# AVkings_mazesolvver-mz1__Sheet_1_2025-12.net
KiCad netlist of a schematic drawn in Altium Designer
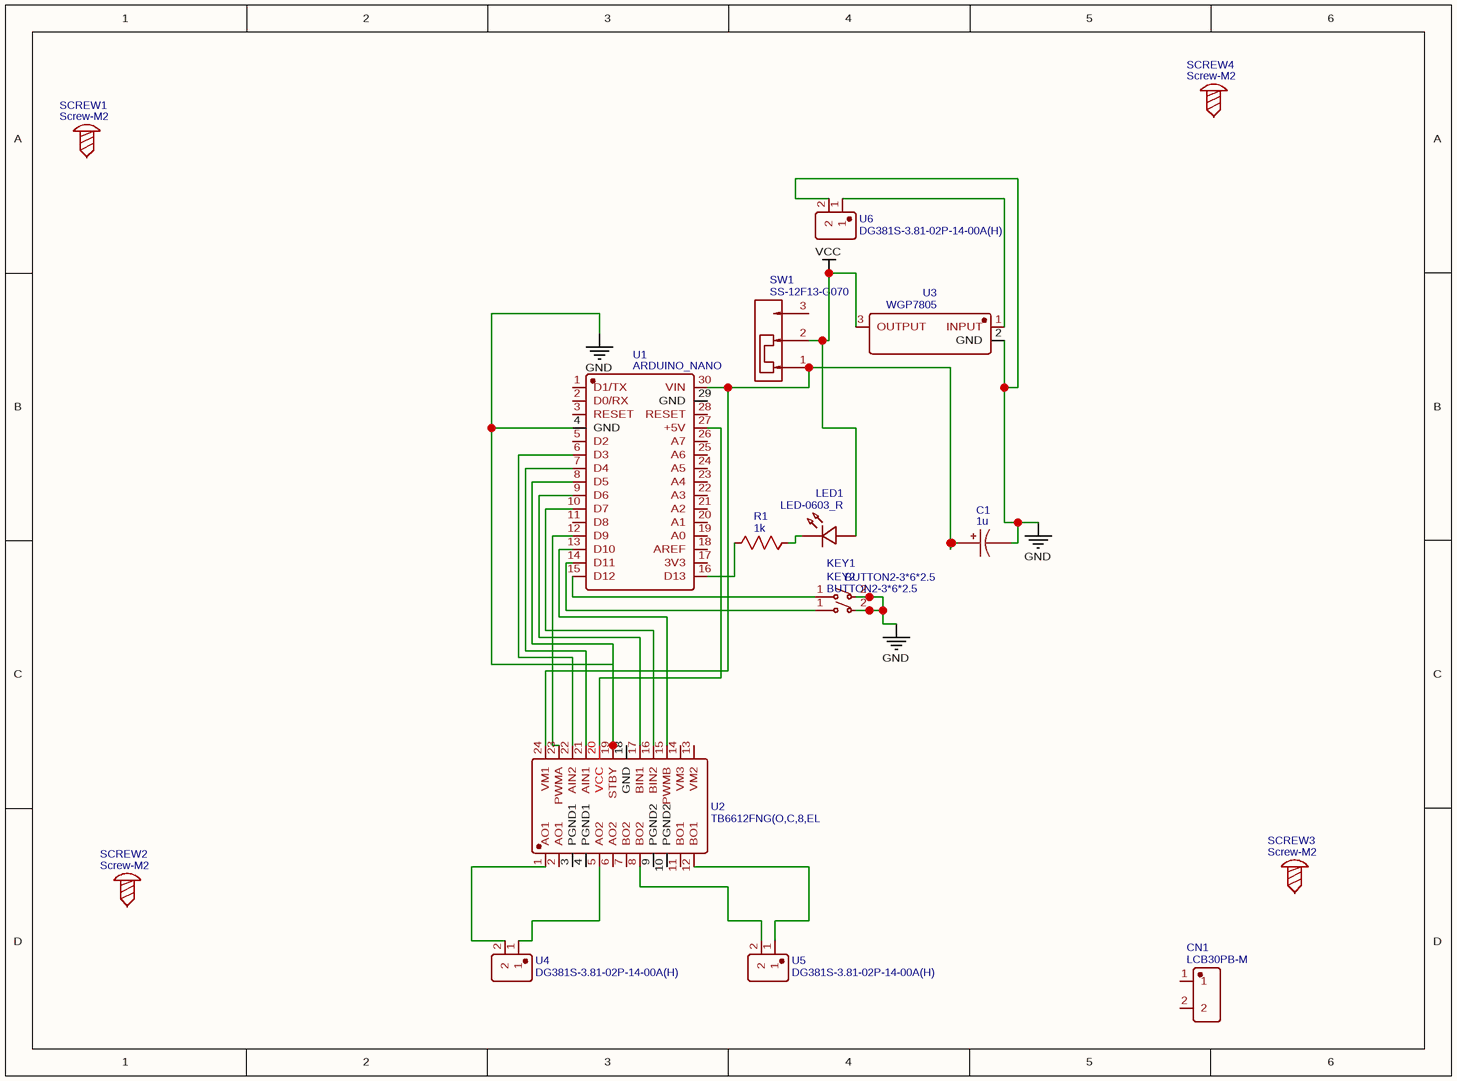
[diagram p0: AVkings_mazesolvver-mz1__Sheet_1_2025-12-17.schdoc]

(export (version "E")
  (design (tool "Eeschema 10.0.6"))
  (components
    (comp (ref "C1")
      (value "1u")
      (fields (field (name "CONTRIBUTOR") "LCEDA_Lib"))
      (libsource (lib "altium-import") (part "root_0_1u_"))
    )
    (comp (ref "CN1")
      (value "LCB30PB-M")
      (fields (field (name "MANUFACTURER") "AMASS(艾迈斯)") (field (name "CONTRIBUTOR") "lcsc"))
      (libsource (lib "altium-import") (part "root_0_LCB30PB-M_"))
    )
    (comp (ref "KEY1")
      (value "BUTTON2-3*6*2.5")
      (fields (field (name "CONTRIBUTOR") "LCSC"))
      (libsource (lib "altium-import") (part "root_0_BUTTON2-3*6*2.5_"))
    )
    (comp (ref "KEY2")
      (value "BUTTON2-3*6*2.5")
      (fields (field (name "CONTRIBUTOR") "LCSC"))
      (libsource (lib "altium-import") (part "root_0_BUTTON2-3*6*2.5_"))
    )
    (comp (ref "LED1")
      (value "LED-0603_R")
      (fields
        (field (name "MANUFACTURER") "EVERLIGHT(台湾亿光)")
        (field (name "MANUFACTURER PART") "19-217/R6C-AL1M2VY/3T")
        (field (name "CONTRIBUTOR") "LCEDA_01")
      )
      (libsource (lib "altium-import") (part "root_0_LED-0603_R_"))
    )
    (comp (ref "R1")
      (value "1k")
      (fields (field (name "CONTRIBUTOR") "LCEDA_Lib"))
      (libsource (lib "altium-import") (part "root_0_1k_"))
    )
    (comp (ref "SCREW1")
      (value "Screw-M2")
      (fields (field (name "CONTRIBUTOR") "EasyEDA"))
      (libsource (lib "altium-import") (part "root_0_Screw-M2_"))
    )
    (comp (ref "SCREW2")
      (value "Screw-M2")
      (fields (field (name "CONTRIBUTOR") "EasyEDA"))
      (libsource (lib "altium-import") (part "root_0_Screw-M2_"))
    )
    (comp (ref "SCREW3")
      (value "Screw-M2")
      (fields (field (name "CONTRIBUTOR") "EasyEDA"))
      (libsource (lib "altium-import") (part "root_0_Screw-M2_"))
    )
    (comp (ref "SCREW4")
      (value "Screw-M2")
      (fields (field (name "CONTRIBUTOR") "EasyEDA"))
      (libsource (lib "altium-import") (part "root_0_Screw-M2_"))
    )
    (comp (ref "SW1")
      (value "SS-12F13-G070")
      (fields (field (name "MANUFACTURER") "G-Switch(品赞)") (field (name "CONTRIBUTOR") "LCSC"))
      (libsource (lib "altium-import") (part "root_1_SS-12F13-G070_"))
    )
    (comp (ref "U1")
      (value "ARDUINO_NANO")
      (fields (field (name "CONTRIBUTOR") "lcsc"))
      (libsource (lib "altium-import") (part "root_0_ARDUINO_NANO_"))
    )
    (comp (ref "U2")
      (value "TB6612FNG(O,C,8,EL")
      (fields (field (name "MANUFACTURER") "TOSHIBA(东芝)"))
      (libsource (lib "altium-import") (part "root_1_TB6612FNG(O,C,8,EL_"))
    )
    (comp (ref "U3")
      (value "WGP7805")
      (fields (field (name "MANUFACTURER") "Wild Goose(威谷)") (field (name "CONTRIBUTOR") "lcsc"))
      (libsource (lib "altium-import") (part "root_0_WGP7805_"))
    )
    (comp (ref "U4")
      (value "DG381S-3.81-02P-14-00A(H)")
      (fields (field (name "MANUFACTURER") "DEGSON(高正/高松)") (field (name "CONTRIBUTOR") "LCSC"))
      (libsource (lib "altium-import") (part "root_3_DG381S-3.81-02P-14-00A(H)_"))
    )
    (comp (ref "U5")
      (value "DG381S-3.81-02P-14-00A(H)")
      (fields (field (name "MANUFACTURER") "DEGSON(高正/高松)") (field (name "CONTRIBUTOR") "LCSC"))
      (libsource (lib "altium-import") (part "root_3_DG381S-3.81-02P-14-00A(H)_"))
    )
    (comp (ref "U6")
      (value "DG381S-3.81-02P-14-00A(H)")
      (fields (field (name "MANUFACTURER") "DEGSON(高正/高松)") (field (name "CONTRIBUTOR") "LCSC"))
      (libsource (lib "altium-import") (part "root_3_DG381S-3.81-02P-14-00A(H)_"))
    )
  )
  (nets
    (net (code "1") (name "GND") (class "Default")
      (node (ref "C1") (pin "2") (pinfunction "2_2") (pintype "passive"))
      (node (ref "KEY1") (pin "2") (pinfunction "2_2") (pintype "passive"))
      (node (ref "KEY2") (pin "2") (pinfunction "2_2") (pintype "passive"))
      (node (ref "U1") (pin "4") (pinfunction "GND_4") (pintype "passive"))
      (node (ref "U1") (pin "8") (pinfunction "D5_8") (pintype "passive"))
      (node (ref "U2") (pin "19") (pinfunction "STBY_19") (pintype "passive"))
      (node (ref "U3") (pin "2") (pinfunction "GND_2") (pintype "passive"))
      (node (ref "U6") (pin "2") (pinfunction "2_2") (pintype "passive"))
    )
    (net (code "2") (name "Net-(LED1-Pad2)") (class "Default")
      (node (ref "LED1") (pin "2") (pinfunction "2_2") (pintype "passive"))
      (node (ref "R1") (pin "2") (pinfunction "2_2") (pintype "passive"))
    )
    (net (code "3") (name "Net-(U1-+5V)") (class "Default")
      (node (ref "U1") (pin "27") (pinfunction "+5V_27") (pintype "passive"))
      (node (ref "U2") (pin "20") (pinfunction "VCC_20") (pintype "passive"))
    )
    (net (code "4") (name "Net-(U1-D3)") (class "Default")
      (node (ref "U1") (pin "6") (pinfunction "D3_6") (pintype "passive"))
      (node (ref "U2") (pin "22") (pinfunction "AIN2_22") (pintype "passive"))
    )
    (net (code "5") (name "Net-(U1-D4)") (class "Default")
      (node (ref "U1") (pin "7") (pinfunction "D4_7") (pintype "passive"))
      (node (ref "U2") (pin "21") (pinfunction "AIN1_21") (pintype "passive"))
    )
    (net (code "6") (name "Net-(U1-D6)") (class "Default")
      (node (ref "U1") (pin "9") (pinfunction "D6_9") (pintype "passive"))
      (node (ref "U2") (pin "17") (pinfunction "BIN1_17") (pintype "passive"))
    )
    (net (code "7") (name "Net-(U1-D7)") (class "Default")
      (node (ref "U1") (pin "10") (pinfunction "D7_10") (pintype "passive"))
      (node (ref "U2") (pin "16") (pinfunction "BIN2_16") (pintype "passive"))
    )
    (net (code "8") (name "Net-(U1-D9)") (class "Default")
      (node (ref "U1") (pin "12") (pinfunction "D9_12") (pintype "passive"))
      (node (ref "U2") (pin "23") (pinfunction "PWMA_23") (pintype "passive"))
    )
    (net (code "9") (name "Net-(U1-D10)") (class "Default")
      (node (ref "U1") (pin "13") (pinfunction "D10_13") (pintype "passive"))
      (node (ref "U2") (pin "15") (pinfunction "PWMB_15") (pintype "passive"))
    )
    (net (code "10") (name "Net-(U1-D11)") (class "Default")
      (node (ref "KEY2") (pin "1") (pinfunction "1_1") (pintype "passive"))
      (node (ref "U1") (pin "14") (pinfunction "D11_14") (pintype "passive"))
    )
    (net (code "11") (name "Net-(U1-D12)") (class "Default")
      (node (ref "KEY1") (pin "1") (pinfunction "1_1") (pintype "passive"))
      (node (ref "U1") (pin "15") (pinfunction "D12_15") (pintype "passive"))
    )
    (net (code "12") (name "Net-(U1-D13)") (class "Default")
      (node (ref "R1") (pin "1") (pinfunction "1_1") (pintype "passive"))
      (node (ref "U1") (pin "16") (pinfunction "D13_16") (pintype "passive"))
    )
    (net (code "13") (name "Net-(U1-VIN)") (class "Default")
      (node (ref "C1") (pin "1") (pinfunction "1_1") (pintype "passive"))
      (node (ref "SW1") (pin "1") (pinfunction "1_1") (pintype "passive"))
      (node (ref "U1") (pin "30") (pinfunction "VIN_30") (pintype "passive"))
      (node (ref "U2") (pin "24") (pinfunction "VM1_24") (pintype "passive"))
    )
    (net (code "14") (name "Net-(U2-AO1-Pad1)") (class "Default")
      (node (ref "U2") (pin "1") (pinfunction "AO1_1") (pintype "passive"))
      (node (ref "U4") (pin "2") (pinfunction "2_2") (pintype "passive"))
    )
    (net (code "15") (name "Net-(U2-AO2-Pad5)") (class "Default")
      (node (ref "U2") (pin "5") (pinfunction "AO2_5") (pintype "passive"))
      (node (ref "U4") (pin "1") (pinfunction "1_1") (pintype "passive"))
    )
    (net (code "16") (name "Net-(U2-BO1-Pad12)") (class "Default")
      (node (ref "U2") (pin "12") (pinfunction "BO1_12") (pintype "passive"))
      (node (ref "U5") (pin "1") (pinfunction "1_1") (pintype "passive"))
    )
    (net (code "17") (name "Net-(U2-BO2-Pad8)") (class "Default")
      (node (ref "U2") (pin "8") (pinfunction "BO2_8") (pintype "passive"))
      (node (ref "U5") (pin "2") (pinfunction "2_2") (pintype "passive"))
    )
    (net (code "18") (name "Net-(U3-INPUT)") (class "Default")
      (node (ref "U3") (pin "1") (pinfunction "INPUT_1") (pintype "passive"))
      (node (ref "U6") (pin "1") (pinfunction "1_1") (pintype "passive"))
    )
    (net (code "19") (name "VCC") (class "Default")
      (node (ref "LED1") (pin "1") (pinfunction "1_1") (pintype "passive"))
      (node (ref "SW1") (pin "2") (pinfunction "2_2") (pintype "passive"))
      (node (ref "U3") (pin "3") (pinfunction "OUTPUT_3") (pintype "passive"))
    )
    (net (code "20") (name "unconnected-(CN1-Pad1)") (class "Default")
      (node (ref "CN1") (pin "1") (pinfunction "1_1") (pintype "passive"))
    )
    (net (code "21") (name "unconnected-(CN1-Pad2)") (class "Default")
      (node (ref "CN1") (pin "2") (pinfunction "2_2") (pintype "passive"))
    )
    (net (code "22") (name "unconnected-(SCREW1-Pad1)") (class "Default")
      (node (ref "SCREW1") (pin "1") (pinfunction "1_1") (pintype "passive"))
    )
    (net (code "23") (name "unconnected-(SCREW2-Pad1)") (class "Default")
      (node (ref "SCREW2") (pin "1") (pinfunction "1_1") (pintype "passive"))
    )
    (net (code "24") (name "unconnected-(SCREW3-Pad1)") (class "Default")
      (node (ref "SCREW3") (pin "1") (pinfunction "1_1") (pintype "passive"))
    )
    (net (code "25") (name "unconnected-(SCREW4-Pad1)") (class "Default")
      (node (ref "SCREW4") (pin "1") (pinfunction "1_1") (pintype "passive"))
    )
    (net (code "26") (name "unconnected-(SW1-Pad3)") (class "Default")
      (node (ref "SW1") (pin "3") (pinfunction "3_3") (pintype "passive"))
    )
    (net (code "27") (name "unconnected-(U1-3V3-Pad17)") (class "Default")
      (node (ref "U1") (pin "17") (pinfunction "3V3_17") (pintype "passive"))
    )
    (net (code "28") (name "unconnected-(U1-A0-Pad19)") (class "Default")
      (node (ref "U1") (pin "19") (pinfunction "A0_19") (pintype "passive"))
    )
    (net (code "29") (name "unconnected-(U1-A1-Pad20)") (class "Default")
      (node (ref "U1") (pin "20") (pinfunction "A1_20") (pintype "passive"))
    )
    (net (code "30") (name "unconnected-(U1-A2-Pad21)") (class "Default")
      (node (ref "U1") (pin "21") (pinfunction "A2_21") (pintype "passive"))
    )
    (net (code "31") (name "unconnected-(U1-A3-Pad22)") (class "Default")
      (node (ref "U1") (pin "22") (pinfunction "A3_22") (pintype "passive"))
    )
    (net (code "32") (name "unconnected-(U1-A4-Pad23)") (class "Default")
      (node (ref "U1") (pin "23") (pinfunction "A4_23") (pintype "passive"))
    )
    (net (code "33") (name "unconnected-(U1-A5-Pad24)") (class "Default")
      (node (ref "U1") (pin "24") (pinfunction "A5_24") (pintype "passive"))
    )
    (net (code "34") (name "unconnected-(U1-A6-Pad25)") (class "Default")
      (node (ref "U1") (pin "25") (pinfunction "A6_25") (pintype "passive"))
    )
    (net (code "35") (name "unconnected-(U1-A7-Pad26)") (class "Default")
      (node (ref "U1") (pin "26") (pinfunction "A7_26") (pintype "passive"))
    )
    (net (code "36") (name "unconnected-(U1-AREF-Pad18)") (class "Default")
      (node (ref "U1") (pin "18") (pinfunction "AREF_18") (pintype "passive"))
    )
    (net (code "37") (name "unconnected-(U1-D0{slash}RX-Pad2)") (class "Default")
      (node (ref "U1") (pin "2") (pinfunction "D0/RX_2") (pintype "passive"))
    )
    (net (code "38") (name "unconnected-(U1-D1{slash}TX-Pad1)") (class "Default")
      (node (ref "U1") (pin "1") (pinfunction "D1/TX_1") (pintype "passive"))
    )
    (net (code "39") (name "unconnected-(U1-D2-Pad5)") (class "Default")
      (node (ref "U1") (pin "5") (pinfunction "D2_5") (pintype "passive"))
    )
    (net (code "40") (name "unconnected-(U1-D8-Pad11)") (class "Default")
      (node (ref "U1") (pin "11") (pinfunction "D8_11") (pintype "passive"))
    )
    (net (code "41") (name "unconnected-(U1-GND-Pad29)") (class "Default")
      (node (ref "U1") (pin "29") (pinfunction "GND_29") (pintype "passive"))
    )
    (net (code "42") (name "unconnected-(U1-RESET-Pad3)") (class "Default")
      (node (ref "U1") (pin "3") (pinfunction "RESET_3") (pintype "passive"))
    )
    (net (code "43") (name "unconnected-(U1-RESET-Pad28)") (class "Default")
      (node (ref "U1") (pin "28") (pinfunction "RESET_28") (pintype "passive"))
    )
    (net (code "44") (name "unconnected-(U2-AO1-Pad2)") (class "Default")
      (node (ref "U2") (pin "2") (pinfunction "AO1_2") (pintype "passive"))
    )
    (net (code "45") (name "unconnected-(U2-AO2-Pad6)") (class "Default")
      (node (ref "U2") (pin "6") (pinfunction "AO2_6") (pintype "passive"))
    )
    (net (code "46") (name "unconnected-(U2-BO1-Pad11)") (class "Default")
      (node (ref "U2") (pin "11") (pinfunction "BO1_11") (pintype "passive"))
    )
    (net (code "47") (name "unconnected-(U2-BO2-Pad7)") (class "Default")
      (node (ref "U2") (pin "7") (pinfunction "BO2_7") (pintype "passive"))
    )
    (net (code "48") (name "unconnected-(U2-GND-Pad18)") (class "Default")
      (node (ref "U2") (pin "18") (pinfunction "GND_18") (pintype "passive"))
    )
    (net (code "49") (name "unconnected-(U2-PGND1-Pad3)") (class "Default")
      (node (ref "U2") (pin "3") (pinfunction "PGND1_3") (pintype "passive"))
    )
    (net (code "50") (name "unconnected-(U2-PGND1-Pad4)") (class "Default")
      (node (ref "U2") (pin "4") (pinfunction "PGND1_4") (pintype "passive"))
    )
    (net (code "51") (name "unconnected-(U2-PGND2-Pad9)") (class "Default")
      (node (ref "U2") (pin "9") (pinfunction "PGND2_9") (pintype "passive"))
    )
    (net (code "52") (name "unconnected-(U2-PGND2-Pad10)") (class "Default")
      (node (ref "U2") (pin "10") (pinfunction "PGND2_10") (pintype "passive"))
    )
    (net (code "53") (name "unconnected-(U2-VM2-Pad13)") (class "Default")
      (node (ref "U2") (pin "13") (pinfunction "VM2_13") (pintype "passive"))
    )
    (net (code "54") (name "unconnected-(U2-VM3-Pad14)") (class "Default")
      (node (ref "U2") (pin "14") (pinfunction "VM3_14") (pintype "passive"))
    )
  )
)
